# Tractive_System_Board_Rev5.net
KiCad netlist of a schematic drawn in EAGLE
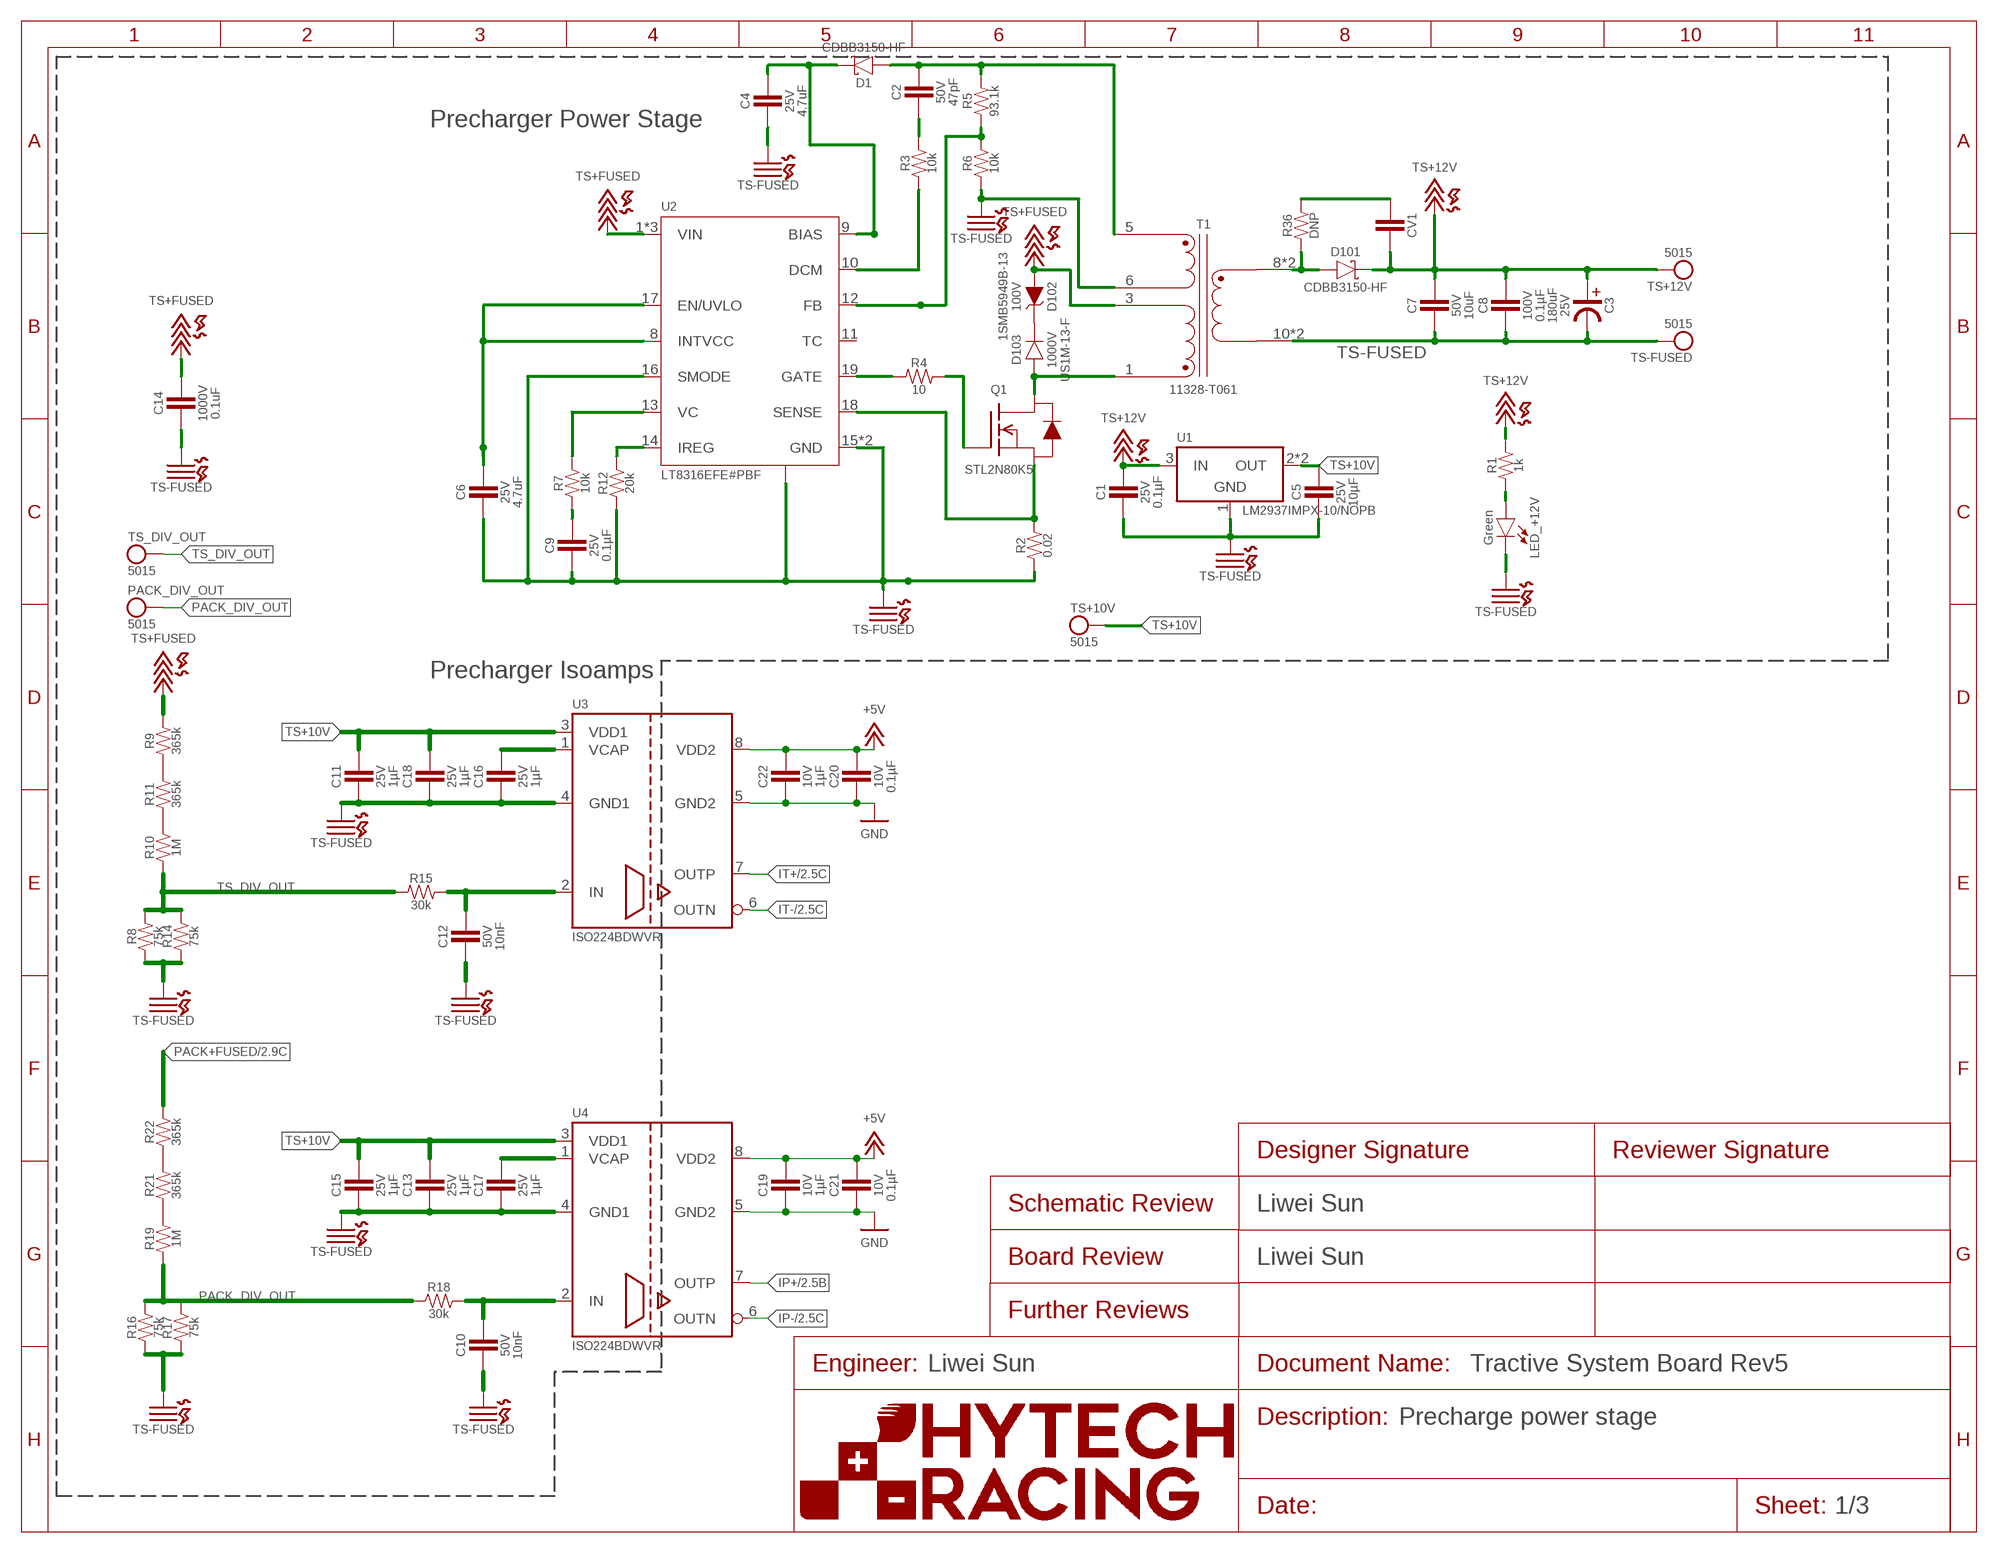
[diagram p0: schematic, sheet 1]
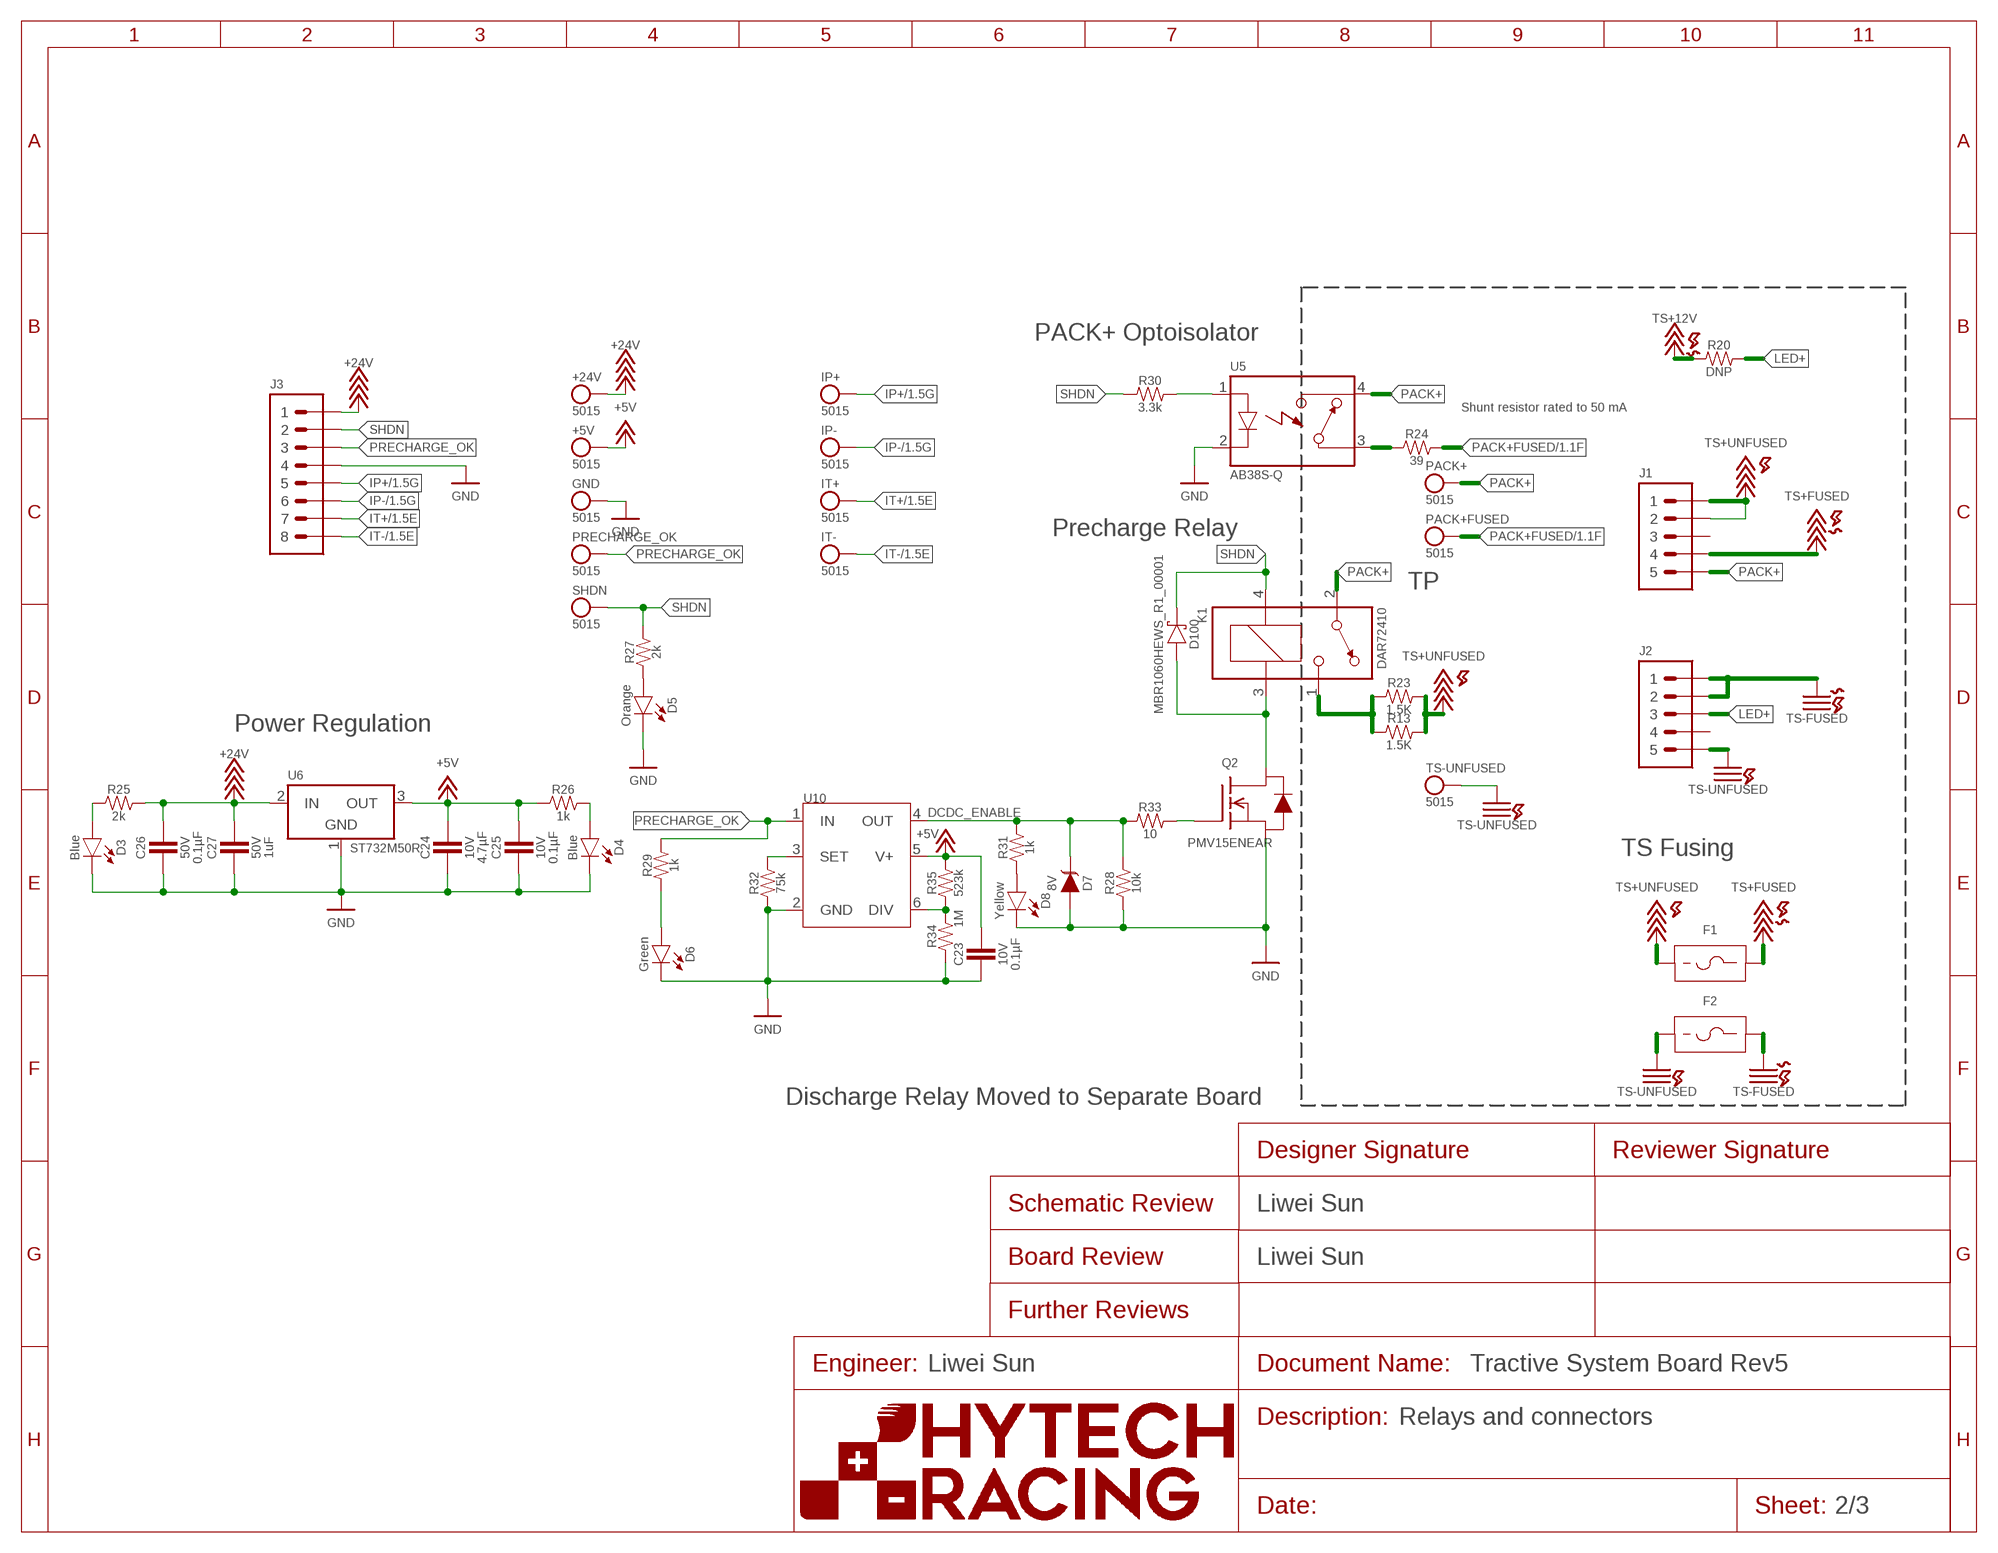
[diagram p1: schematic, sheet 2]
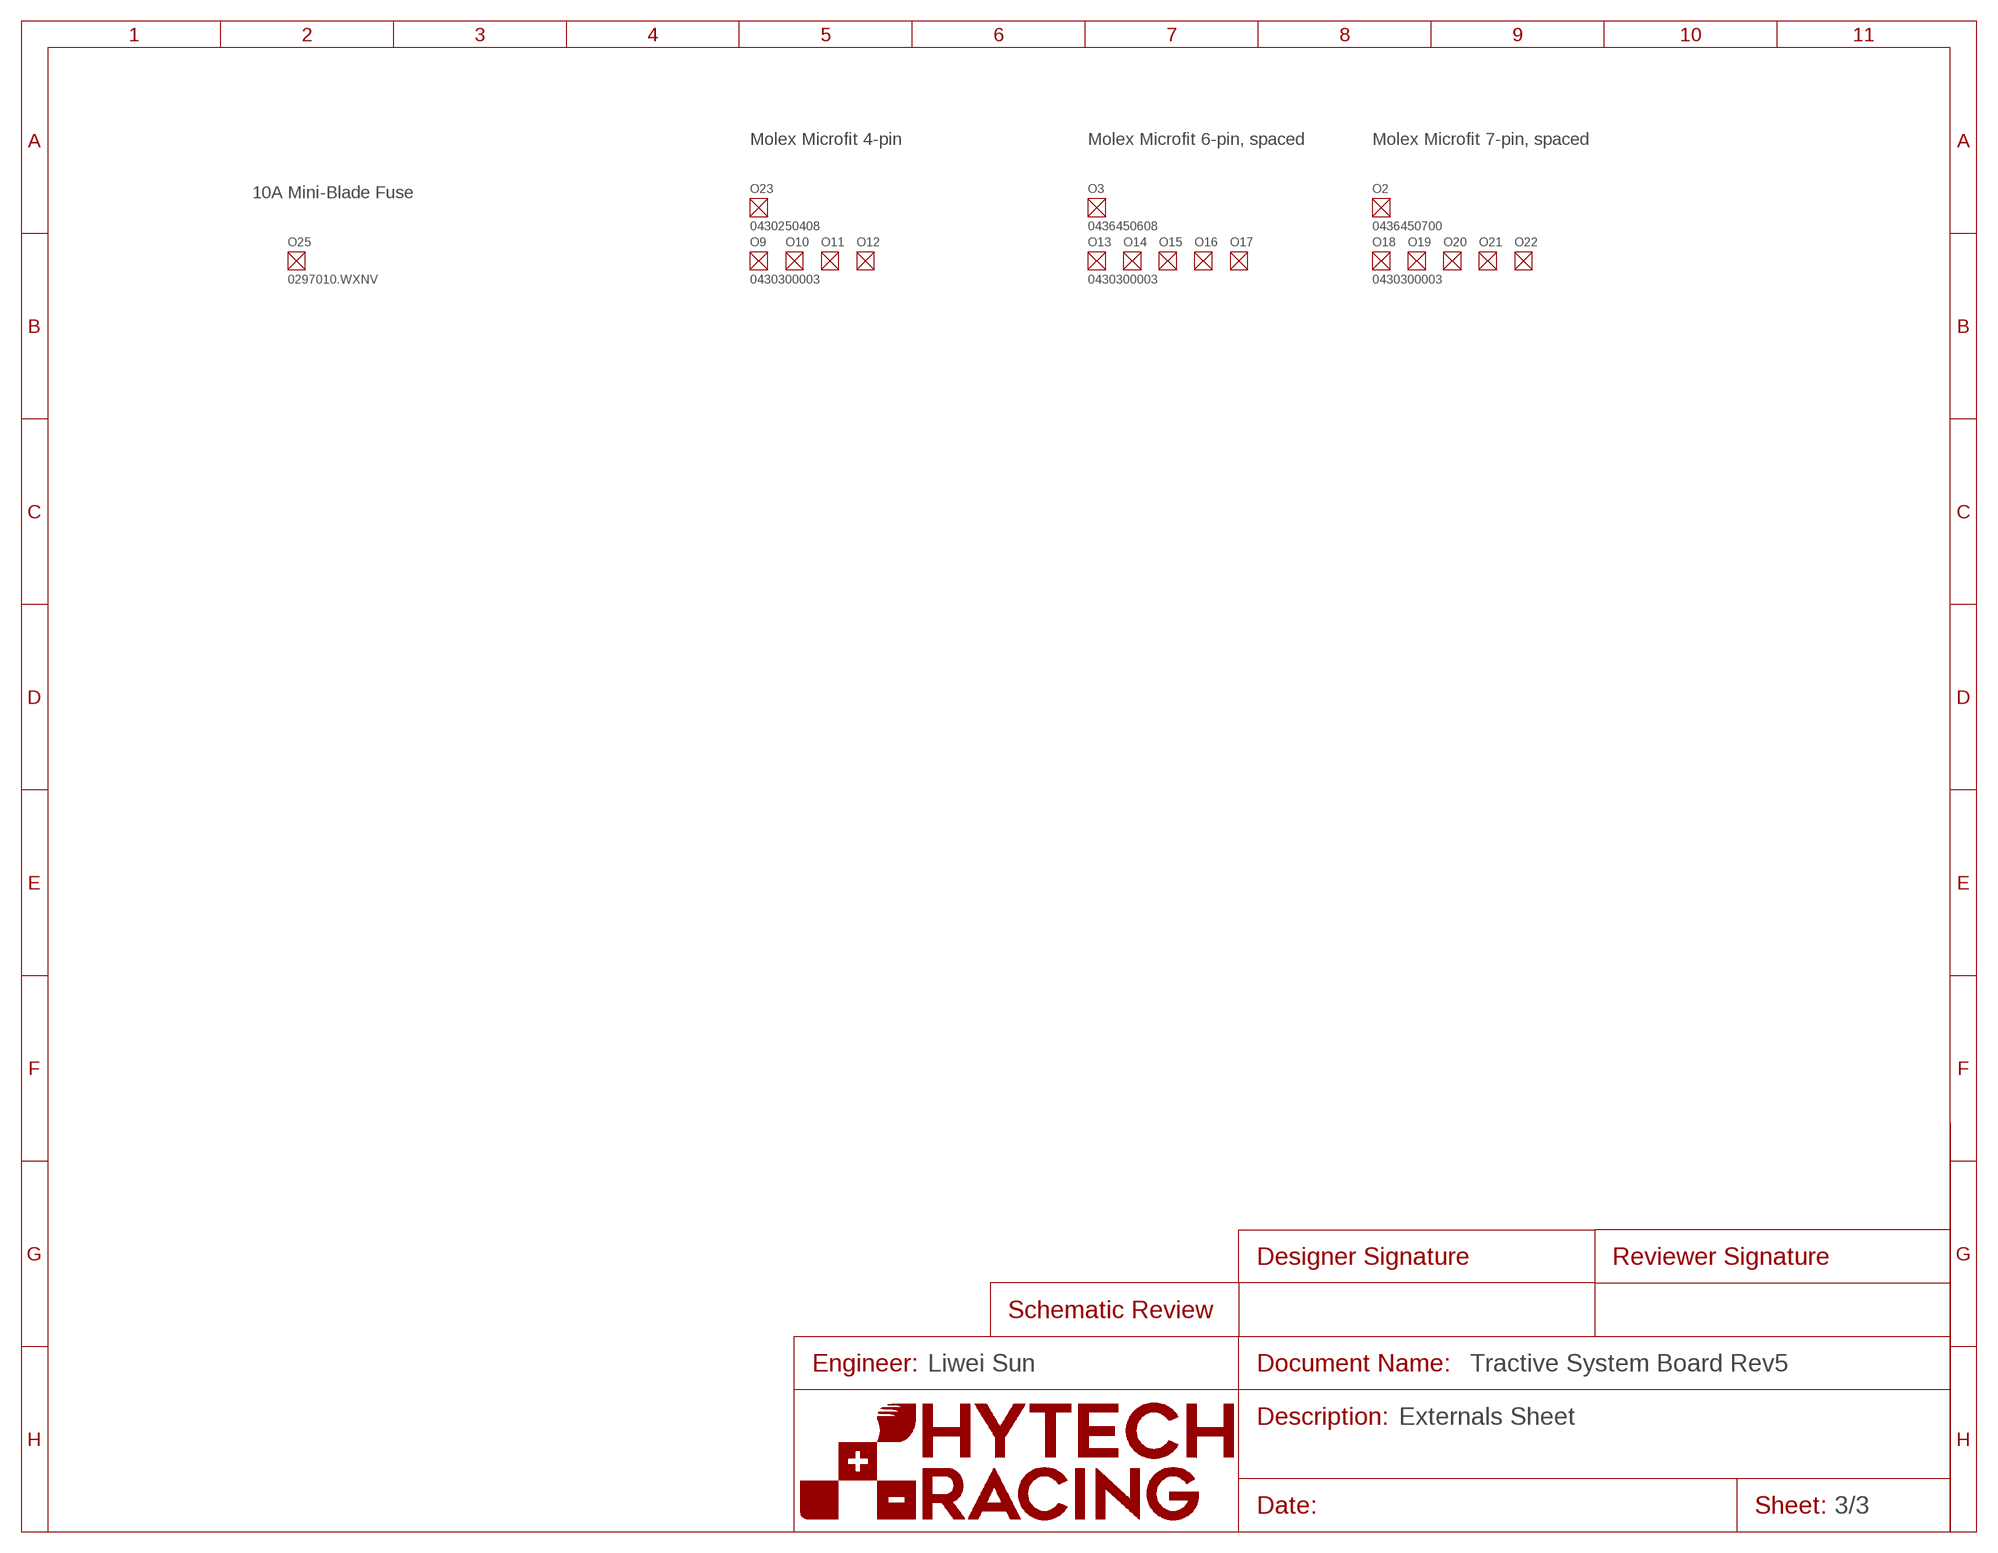
[diagram p2: schematic, sheet 3]

(export (version "E")
  (design (tool "Eeschema 10.0.6"))
  (components
    (comp (ref "C1")
      (value "CAPACITOR_0603_25V_0.1UF")
      (footprint "eagle-import:0603-CAP")
      (fields
        (field (name "CAPACITANCE") "0.1µF")
        (field (name "MANUFACTURER") "Samsung Electro-Mechanics")
        (field (name "MPN") "CL10B104KA8NNNC")
        (field (name "TOLERANCE") "10%")
        (field (name "VOLTAGE") "25V")
      )
      (libsource (lib "eagle-import") (part "CAPACITOR_?_060325V_0.1UF"))
    )
    (comp (ref "C2")
      (value "CAPACITOR_0603_50V_47PF")
      (footprint "eagle-import:0603-CAP")
      (fields
        (field (name "CAPACITANCE") "47pF")
        (field (name "MANUFACTURER") "TDK Corporation")
        (field (name "MPN") "CGA3E2NP01H470J080AA")
        (field (name "TOLERANCE") "5%")
        (field (name "VOLTAGE") "50V")
      )
      (libsource (lib "eagle-import") (part "CAPACITOR_?_060350V_47PF"))
    )
    (comp (ref "C3")
      (value "CAPACITOR_ELECTROLYTIC_A759_180UF")
      (footprint "eagle-import:A759")
      (fields
        (field (name "CAPACITANCE") "180uF")
        (field (name "MANUFACTURER") "KEMET")
        (field (name "MPN") "A759KR187M1VAAE024")
        (field (name "TOLERANCE") "20%")
        (field (name "VOLTAGE") "25V")
      )
      (libsource (lib "eagle-import") (part "CAPACITOR_ELECTROLYTIC_?_A759180UF"))
    )
    (comp (ref "C4")
      (value "CAPACITOR_0603_25V_4.7UF")
      (footprint "eagle-import:0603-CAP")
      (fields
        (field (name "CAPACITANCE") "4.7uF")
        (field (name "MANUFACTURER") "TDK Corporation")
        (field (name "MPN") " C1608X5R1E475K080AC")
        (field (name "TOLERANCE") "10%")
        (field (name "VOLTAGE") "25V")
      )
      (libsource (lib "eagle-import") (part "CAPACITOR_?_060325V_4.7UF"))
    )
    (comp (ref "C5")
      (value "CAPACITOR_0603_25V_10UF")
      (footprint "eagle-import:0603-CAP")
      (fields
        (field (name "CAPACITANCE") "10µF")
        (field (name "MANUFACTURER") "Murata Electronics")
        (field (name "MPN") "GRM188R61E106MA73D")
        (field (name "TOLERANCE") "20%")
        (field (name "VOLTAGE") "25V")
      )
      (libsource (lib "eagle-import") (part "CAPACITOR_?_060325V_10UF"))
    )
    (comp (ref "C6")
      (value "CAPACITOR_0603_25V_4.7UF")
      (footprint "eagle-import:0603-CAP")
      (fields
        (field (name "CAPACITANCE") "4.7uF")
        (field (name "MANUFACTURER") "TDK Corporation")
        (field (name "MPN") " C1608X5R1E475K080AC")
        (field (name "TOLERANCE") "10%")
        (field (name "VOLTAGE") "25V")
      )
      (libsource (lib "eagle-import") (part "CAPACITOR_?_060325V_4.7UF"))
    )
    (comp (ref "C7")
      (value "CAPACITOR_0805_50V_10UF")
      (footprint "eagle-import:0805-CAP")
      (fields
        (field (name "CAPACITANCE") "10uF")
        (field (name "MANUFACTURER") "Murata")
        (field (name "MPN") " GRM21BR61H106KE43L")
        (field (name "TOLERANCE") "10%")
        (field (name "VOLTAGE") "50V")
      )
      (libsource (lib "eagle-import") (part "CAPACITOR_?_080550V_10UF"))
    )
    (comp (ref "C8")
      (value "CAPACITOR_0603_100V_0.1UF")
      (footprint "eagle-import:0603-CAP")
      (fields
        (field (name "CAPACITANCE") "0.1µF")
        (field (name "MANUFACTURER") "Yageo")
        (field (name "MPN") "CC0603KRX7R0BB104")
        (field (name "TOLERANCE") "10%")
        (field (name "VOLTAGE") "100V")
      )
      (libsource (lib "eagle-import") (part "CAPACITOR_?_0603100V_0.1UF"))
    )
    (comp (ref "C9")
      (value "CAPACITOR_0603_25V_0.1UF")
      (footprint "eagle-import:0603-CAP")
      (fields
        (field (name "CAPACITANCE") "0.1µF")
        (field (name "MANUFACTURER") "Samsung Electro-Mechanics")
        (field (name "MPN") "CL10B104KA8NNNC")
        (field (name "TOLERANCE") "10%")
        (field (name "VOLTAGE") "25V")
      )
      (libsource (lib "eagle-import") (part "CAPACITOR_?_060325V_0.1UF"))
    )
    (comp (ref "C10")
      (value "CAPACITOR_0603_50V_10NF")
      (footprint "eagle-import:0603-CAP")
      (fields
        (field (name "CAPACITANCE") "10nF")
        (field (name "MANUFACTURER") "TDK Corporation")
        (field (name "MPN") "C1608C0G1H103J080AA")
        (field (name "TOLERANCE") "5%")
        (field (name "VOLTAGE") "50V")
      )
      (libsource (lib "eagle-import") (part "CAPACITOR_?_060350V_10NF"))
    )
    (comp (ref "C11")
      (value "CAPACITOR_0603_25V_1UF")
      (footprint "eagle-import:0603-CAP")
      (fields
        (field (name "CAPACITANCE") "1µF")
        (field (name "MANUFACTURER") "Samsung Electro-Mechanics")
        (field (name "MPN") "CL10B105KA8NNNC")
        (field (name "TOLERANCE") "10%")
        (field (name "VOLTAGE") "25V")
      )
      (libsource (lib "eagle-import") (part "CAPACITOR_?_060325V_1UF"))
    )
    (comp (ref "C12")
      (value "CAPACITOR_0603_50V_10NF")
      (footprint "eagle-import:0603-CAP")
      (fields
        (field (name "CAPACITANCE") "10nF")
        (field (name "MANUFACTURER") "TDK Corporation")
        (field (name "MPN") "C1608C0G1H103J080AA")
        (field (name "TOLERANCE") "5%")
        (field (name "VOLTAGE") "50V")
      )
      (libsource (lib "eagle-import") (part "CAPACITOR_?_060350V_10NF"))
    )
    (comp (ref "C13")
      (value "CAPACITOR_0603_25V_1UF")
      (footprint "eagle-import:0603-CAP")
      (fields
        (field (name "CAPACITANCE") "1µF")
        (field (name "MANUFACTURER") "Samsung Electro-Mechanics")
        (field (name "MPN") "CL10B105KA8NNNC")
        (field (name "TOLERANCE") "10%")
        (field (name "VOLTAGE") "25V")
      )
      (libsource (lib "eagle-import") (part "CAPACITOR_?_060325V_1UF"))
    )
    (comp (ref "C14")
      (value "CAPACITOR_1812_1000V_0.1UF")
      (footprint "eagle-import:1812-CAP")
      (fields
        (field (name "CAPACITANCE") "0.1uF")
        (field (name "MANUFACTURER") "KEMET")
        (field (name "MPN") "C1812W104KDRAC7800")
        (field (name "TOLERANCE") "10%")
        (field (name "VOLTAGE") "1000V")
      )
      (libsource (lib "eagle-import") (part "CAPACITOR_?_18121000V_0.1UF"))
    )
    (comp (ref "C15")
      (value "CAPACITOR_0603_25V_1UF")
      (footprint "eagle-import:0603-CAP")
      (fields
        (field (name "CAPACITANCE") "1µF")
        (field (name "MANUFACTURER") "Samsung Electro-Mechanics")
        (field (name "MPN") "CL10B105KA8NNNC")
        (field (name "TOLERANCE") "10%")
        (field (name "VOLTAGE") "25V")
      )
      (libsource (lib "eagle-import") (part "CAPACITOR_?_060325V_1UF"))
    )
    (comp (ref "C16")
      (value "CAPACITOR_0603_25V_1UF")
      (footprint "eagle-import:0603-CAP")
      (fields
        (field (name "CAPACITANCE") "1µF")
        (field (name "MANUFACTURER") "Samsung Electro-Mechanics")
        (field (name "MPN") "CL10B105KA8NNNC")
        (field (name "TOLERANCE") "10%")
        (field (name "VOLTAGE") "25V")
      )
      (libsource (lib "eagle-import") (part "CAPACITOR_?_060325V_1UF"))
    )
    (comp (ref "C17")
      (value "CAPACITOR_0603_25V_1UF")
      (footprint "eagle-import:0603-CAP")
      (fields
        (field (name "CAPACITANCE") "1µF")
        (field (name "MANUFACTURER") "Samsung Electro-Mechanics")
        (field (name "MPN") "CL10B105KA8NNNC")
        (field (name "TOLERANCE") "10%")
        (field (name "VOLTAGE") "25V")
      )
      (libsource (lib "eagle-import") (part "CAPACITOR_?_060325V_1UF"))
    )
    (comp (ref "C18")
      (value "CAPACITOR_0603_25V_1UF")
      (footprint "eagle-import:0603-CAP")
      (fields
        (field (name "CAPACITANCE") "1µF")
        (field (name "MANUFACTURER") "Samsung Electro-Mechanics")
        (field (name "MPN") "CL10B105KA8NNNC")
        (field (name "TOLERANCE") "10%")
        (field (name "VOLTAGE") "25V")
      )
      (libsource (lib "eagle-import") (part "CAPACITOR_?_060325V_1UF"))
    )
    (comp (ref "C19")
      (value "CAPACITOR_0603_10V_1UF")
      (footprint "eagle-import:0603-CAP")
      (fields
        (field (name "CAPACITANCE") "1µF")
        (field (name "MANUFACTURER") "Yageo")
        (field (name "MPN") "CC0603KRX7R6BB105")
        (field (name "TOLERANCE") "10%")
        (field (name "VOLTAGE") "10V")
      )
      (libsource (lib "eagle-import") (part "CAPACITOR_?_060310V_1UF"))
    )
    (comp (ref "C20")
      (value "CAPACITOR_0603_10V_0.1UF")
      (footprint "eagle-import:0603-CAP")
      (fields
        (field (name "CAPACITANCE") "0.1µF")
        (field (name "MANUFACTURER") "Vishay Vitramon")
        (field (name "MPN") "VJ0603Y104JXQPW1BC")
        (field (name "TOLERANCE") "5%")
        (field (name "VOLTAGE") "10V")
      )
      (libsource (lib "eagle-import") (part "CAPACITOR_?_060310V_0.1UF"))
    )
    (comp (ref "C21")
      (value "CAPACITOR_0603_10V_0.1UF")
      (footprint "eagle-import:0603-CAP")
      (fields
        (field (name "CAPACITANCE") "0.1µF")
        (field (name "MANUFACTURER") "Vishay Vitramon")
        (field (name "MPN") "VJ0603Y104JXQPW1BC")
        (field (name "TOLERANCE") "5%")
        (field (name "VOLTAGE") "10V")
      )
      (libsource (lib "eagle-import") (part "CAPACITOR_?_060310V_0.1UF"))
    )
    (comp (ref "C22")
      (value "CAPACITOR_0603_10V_1UF")
      (footprint "eagle-import:0603-CAP")
      (fields
        (field (name "CAPACITANCE") "1µF")
        (field (name "MANUFACTURER") "Yageo")
        (field (name "MPN") "CC0603KRX7R6BB105")
        (field (name "TOLERANCE") "10%")
        (field (name "VOLTAGE") "10V")
      )
      (libsource (lib "eagle-import") (part "CAPACITOR_?_060310V_1UF"))
    )
    (comp (ref "CV1")
      (value "CAPACITOR_VALUE")
      (footprint "eagle-import:0603-CAP")
      (libsource (lib "eagle-import") (part "CAPACITOR_VALUE"))
    )
    (comp (ref "D1")
      (value "SCHOTTKY_DO-214AA_150V")
      (footprint "eagle-import:DO-214AA")
      (fields
        (field (name "MANUFACTURER") "Comchip Technology")
        (field (name "MPN") "CDBB3150-HF")
        (field (name "VOLTAGE") "150V")
      )
      (libsource (lib "eagle-import") (part "SCHOTTKY_?_DO-214AA150V"))
    )
    (comp (ref "D101")
      (value "SCHOTTKY_DO-214AA_150V")
      (footprint "eagle-import:DO-214AA")
      (fields
        (field (name "MANUFACTURER") "Comchip Technology")
        (field (name "MPN") "CDBB3150-HF")
        (field (name "VOLTAGE") "150V")
      )
      (libsource (lib "eagle-import") (part "SCHOTTKY_?_DO-214AA150V"))
    )
    (comp (ref "D102")
      (value "ZENER_DO-214AA_100V")
      (footprint "eagle-import:DO-214AA")
      (fields
        (field (name "MANUFACTURER") "Diodes Incorporated")
        (field (name "MPN") "1SMB5949B-13")
        (field (name "VOLTAGE") "100V")
      )
      (libsource (lib "eagle-import") (part "ZENER_?_DO-214AA100V"))
    )
    (comp (ref "D103")
      (value "RECTIFIER_1000V_SMA")
      (footprint "eagle-import:SMA")
      (fields
        (field (name "MANUFACTURER") "Diodes Incorporated")
        (field (name "MPN") "US1M-13-F")
        (field (name "VOLTAGE") "1000V")
      )
      (libsource (lib "eagle-import") (part "RECTIFIER__?SMA1000V"))
    )
    (comp (ref "LED_+12V")
      (value "LED_0603_GREEN")
      (footprint "eagle-import:0603-LED")
      (fields
        (field (name "COLOR") "Green")
        (field (name "MANUFACTURER") "Kingbright")
        (field (name "MPN") "APT1608ZGCK")
      )
      (libsource (lib "eagle-import") (part "LED_?_0603GREEN"))
    )
    (comp (ref "PACK_DIV_OUT")
      (value "TEST_POINT")
      (footprint "eagle-import:5015")
      (fields (field (name "MPN") "5015") (field (name "MANUFACTURER") "Keystone Electronics"))
      (libsource (lib "eagle-import") (part "TEST_POINT"))
    )
    (comp (ref "Q1")
      (value "TRANSISTOR_N_MOS_POWERFLAT5X6_STL2N80K5")
      (footprint "eagle-import:POWERFLAT5X6")
      (fields (field (name "MANUFACTURER") "STMicroelectronics") (field (name "MPN") "STL2N80K5"))
      (libsource (lib "eagle-import") (part "TRANSISTOR_N_MOS_?_POWERFLAT5X6STL2N80K5"))
    )
    (comp (ref "R1")
      (value "RESISTOR_0603_1K")
      (footprint "eagle-import:0603-RES")
      (fields
        (field (name "MANUFACTURER") "TE Connectivity Passive Product")
        (field (name "MPN") " CPF-A-0603B1K0E")
        (field (name "POWER") "0.0625W")
        (field (name "RESISTANCE") "1k")
      )
      (libsource (lib "eagle-import") (part "RESISTOR_?_06031K"))
    )
    (comp (ref "R2")
      (value "RESISTOR_0603_0.02")
      (footprint "eagle-import:0603-RES")
      (fields
        (field (name "MANUFACTURER") "Panasonic Electronic Components")
        (field (name "MPN") "ERJ-3BWFR020V")
        (field (name "POWER") "0.33W")
        (field (name "RESISTANCE") "0.02")
      )
      (libsource (lib "eagle-import") (part "RESISTOR_?_06030.02"))
    )
    (comp (ref "R3")
      (value "RESISTOR_0603_10K")
      (footprint "eagle-import:0603-RES")
      (fields
        (field (name "MANUFACTURER") "Panasonic Electronic Components")
        (field (name "MPN") "ERA-3ARB103V")
        (field (name "POWER") "0.1W")
        (field (name "RESISTANCE") "10k")
      )
      (libsource (lib "eagle-import") (part "RESISTOR_?_060310K"))
    )
    (comp (ref "R4")
      (value "RESISTOR_0603_10")
      (footprint "eagle-import:0603-RES")
      (fields
        (field (name "MANUFACTURER") "Yageo")
        (field (name "MPN") "RC0603FR-0710RL")
        (field (name "POWER") "0.1W")
        (field (name "RESISTANCE") "10")
      )
      (libsource (lib "eagle-import") (part "RESISTOR_?_060310"))
    )
    (comp (ref "R5")
      (value "RESISTOR_0603_93.1K")
      (footprint "eagle-import:0603-RES")
      (fields
        (field (name "MANUFACTURER") "Panasonic Electronic Components")
        (field (name "MPN") "ERJ-PB3B9312V")
        (field (name "POWER") "0.2W")
        (field (name "RESISTANCE") "93.1k")
      )
      (libsource (lib "eagle-import") (part "RESISTOR_?_060393.1K"))
    )
    (comp (ref "R6")
      (value "RESISTOR_0603_10K")
      (footprint "eagle-import:0603-RES")
      (fields
        (field (name "MANUFACTURER") "Panasonic Electronic Components")
        (field (name "MPN") "ERA-3ARB103V")
        (field (name "POWER") "0.1W")
        (field (name "RESISTANCE") "10k")
      )
      (libsource (lib "eagle-import") (part "RESISTOR_?_060310K"))
    )
    (comp (ref "R7")
      (value "RESISTOR_0603_10K")
      (footprint "eagle-import:0603-RES")
      (fields
        (field (name "MANUFACTURER") "Panasonic Electronic Components")
        (field (name "MPN") "ERA-3ARB103V")
        (field (name "POWER") "0.1W")
        (field (name "RESISTANCE") "10k")
      )
      (libsource (lib "eagle-import") (part "RESISTOR_?_060310K"))
    )
    (comp (ref "R8")
      (value "RESISTOR_0805_HV75K")
      (footprint "eagle-import:0805-RES")
      (fields
        (field (name "MANUFACTURER") "Rohm Semiconductor")
        (field (name "MPN") "KTR10EZPF7502 ")
        (field (name "POWER") "0.125W")
        (field (name "RESISTANCE") "75k")
      )
      (libsource (lib "eagle-import") (part "RESISTOR_?_0805HV75K"))
    )
    (comp (ref "R9")
      (value "RESISTOR_0805_HV365K")
      (footprint "eagle-import:0805-RES")
      (fields
        (field (name "MANUFACTURER") "Rohm")
        (field (name "MPN") "KTR10EZPF3653")
        (field (name "POWER") "0.125W")
        (field (name "RESISTANCE") "365k")
      )
      (libsource (lib "eagle-import") (part "RESISTOR_?_0805HV365K"))
    )
    (comp (ref "R10")
      (value "RESISTOR_0805_HV1M")
      (footprint "eagle-import:0805-RES")
      (fields
        (field (name "MANUFACTURER") "Rohm Semiconductor")
        (field (name "MPN") "KTR10EZPF1004")
        (field (name "POWER") "0.125W")
        (field (name "RESISTANCE") "1M")
      )
      (libsource (lib "eagle-import") (part "RESISTOR_?_0805HV1M"))
    )
    (comp (ref "R11")
      (value "RESISTOR_0805_HV365K")
      (footprint "eagle-import:0805-RES")
      (fields
        (field (name "MANUFACTURER") "Rohm")
        (field (name "MPN") "KTR10EZPF3653")
        (field (name "POWER") "0.125W")
        (field (name "RESISTANCE") "365k")
      )
      (libsource (lib "eagle-import") (part "RESISTOR_?_0805HV365K"))
    )
    (comp (ref "R12")
      (value "RESISTOR_0603_20K")
      (footprint "eagle-import:0603-RES")
      (fields
        (field (name "MANUFACTURER") "Yageo")
        (field (name "MPN") "RC0603FR-0720KL")
        (field (name "POWER") "0.1 W")
        (field (name "RESISTANCE") "20k")
      )
      (libsource (lib "eagle-import") (part "RESISTOR_?_060320K"))
    )
    (comp (ref "R14")
      (value "RESISTOR_0805_HV75K")
      (footprint "eagle-import:0805-RES")
      (fields
        (field (name "MANUFACTURER") "Rohm Semiconductor")
        (field (name "MPN") "KTR10EZPF7502 ")
        (field (name "POWER") "0.125W")
        (field (name "RESISTANCE") "75k")
      )
      (libsource (lib "eagle-import") (part "RESISTOR_?_0805HV75K"))
    )
    (comp (ref "R15")
      (value "RESISTOR_0603_")
      (footprint "eagle-import:0603-RES")
      (fields
        (field (name "MANUFACTURER") "Panasonic Electronic Components")
        (field (name "MPN") "ERA-3ARB303V")
        (field (name "POWER") "0.1W")
        (field (name "RESISTANCE") "30k")
      )
      (libsource (lib "eagle-import") (part "RESISTOR_?_060330K"))
    )
    (comp (ref "R16")
      (value "RESISTOR_0805_HV75K")
      (footprint "eagle-import:0805-RES")
      (fields
        (field (name "MANUFACTURER") "Rohm Semiconductor")
        (field (name "MPN") "KTR10EZPF7502 ")
        (field (name "POWER") "0.125W")
        (field (name "RESISTANCE") "75k")
      )
      (libsource (lib "eagle-import") (part "RESISTOR_?_0805HV75K"))
    )
    (comp (ref "R17")
      (value "RESISTOR_0805_HV75K")
      (footprint "eagle-import:0805-RES")
      (fields
        (field (name "MANUFACTURER") "Rohm Semiconductor")
        (field (name "MPN") "KTR10EZPF7502 ")
        (field (name "POWER") "0.125W")
        (field (name "RESISTANCE") "75k")
      )
      (libsource (lib "eagle-import") (part "RESISTOR_?_0805HV75K"))
    )
    (comp (ref "R18")
      (value "RESISTOR_0603_")
      (footprint "eagle-import:0603-RES")
      (fields
        (field (name "MANUFACTURER") "Panasonic Electronic Components")
        (field (name "MPN") "ERA-3ARB303V")
        (field (name "POWER") "0.1W")
        (field (name "RESISTANCE") "30k")
      )
      (libsource (lib "eagle-import") (part "RESISTOR_?_060330K"))
    )
    (comp (ref "R19")
      (value "RESISTOR_0805_HV1M")
      (footprint "eagle-import:0805-RES")
      (fields
        (field (name "MANUFACTURER") "Rohm Semiconductor")
        (field (name "MPN") "KTR10EZPF1004")
        (field (name "POWER") "0.125W")
        (field (name "RESISTANCE") "1M")
      )
      (libsource (lib "eagle-import") (part "RESISTOR_?_0805HV1M"))
    )
    (comp (ref "R21")
      (value "RESISTOR_0805_HV365K")
      (footprint "eagle-import:0805-RES")
      (fields
        (field (name "MANUFACTURER") "Rohm")
        (field (name "MPN") "KTR10EZPF3653")
        (field (name "POWER") "0.125W")
        (field (name "RESISTANCE") "365k")
      )
      (libsource (lib "eagle-import") (part "RESISTOR_?_0805HV365K"))
    )
    (comp (ref "R22")
      (value "RESISTOR_0805_HV365K")
      (footprint "eagle-import:0805-RES")
      (fields
        (field (name "MANUFACTURER") "Rohm")
        (field (name "MPN") "KTR10EZPF3653")
        (field (name "POWER") "0.125W")
        (field (name "RESISTANCE") "365k")
      )
      (libsource (lib "eagle-import") (part "RESISTOR_?_0805HV365K"))
    )
    (comp (ref "R36")
      (value "RESISTOR_0603_DNP")
      (footprint "eagle-import:0603-RES")
      (fields (field (name "RESISTANCE") "DNP"))
      (libsource (lib "eagle-import") (part "RESISTOR_?_0603DNP"))
    )
    (comp (ref "T1")
      (value "TRANSFORMER(3W)")
      (footprint "eagle-import:PQ2620")
      (fields (field (name "MPN") "11328-T061") (field (name "MANUFACTURER") "Sumida"))
      (libsource (lib "eagle-import") (part "TRANSFORMER(3W)"))
    )
    (comp (ref "TS+10V")
      (value "TEST_POINT")
      (footprint "eagle-import:5015")
      (fields (field (name "MPN") "5015") (field (name "MANUFACTURER") "Keystone Electronics"))
      (libsource (lib "eagle-import") (part "TEST_POINT"))
    )
    (comp (ref "TS+12V")
      (value "TEST_POINT")
      (footprint "eagle-import:5015")
      (fields (field (name "MPN") "5015") (field (name "MANUFACTURER") "Keystone Electronics"))
      (libsource (lib "eagle-import") (part "TEST_POINT"))
    )
    (comp (ref "TS-FUSED")
      (value "TEST_POINT")
      (footprint "eagle-import:5015")
      (fields (field (name "MPN") "5015") (field (name "MANUFACTURER") "Keystone Electronics"))
      (libsource (lib "eagle-import") (part "TEST_POINT"))
    )
    (comp (ref "TS_DIV_OUT")
      (value "TEST_POINT")
      (footprint "eagle-import:5015")
      (fields (field (name "MPN") "5015") (field (name "MANUFACTURER") "Keystone Electronics"))
      (libsource (lib "eagle-import") (part "TEST_POINT"))
    )
    (comp (ref "U1")
      (value "VOLTAGE_REGULATOR_SOT-223_10V")
      (footprint "eagle-import:SOT-223")
      (fields (field (name "MANUFACTURER") "Texas Instruments") (field (name "MPN") " LM2937IMPX-10/NOPB"))
      (libsource (lib "eagle-import") (part "VOLTAGE_REGULATOR_?_SOT-22310V"))
    )
    (comp (ref "U2")
      (value "LT8316")
      (footprint "eagle-import:TSSOP-20(16)")
      (fields (field (name "MPN") "LT8316EFE#PBF") (field (name "MANUFACTURER") "Analog Devices"))
      (libsource (lib "eagle-import") (part "LT8316"))
    )
    (comp (ref "U3")
      (value "ISO224B_AIRGAP")
      (footprint "eagle-import:SOIC-08(WIDE,0.295_)-AIRGAP")
      (fields (field (name "MANUFACTURER") "Texas Instruments") (field (name "MPN") "ISO224BDWVR"))
      (libsource (lib "eagle-import") (part "ISO224_AIRGAPB"))
    )
    (comp (ref "U4")
      (value "ISO224B_AIRGAP")
      (footprint "eagle-import:SOIC-08(WIDE,0.295_)-AIRGAP")
      (fields (field (name "MANUFACTURER") "Texas Instruments") (field (name "MPN") "ISO224BDWVR"))
      (libsource (lib "eagle-import") (part "ISO224_AIRGAPB"))
    )
    (comp (ref "+5V")
      (value "TEST_POINT")
      (footprint "eagle-import:5015")
      (fields (field (name "MPN") "5015") (field (name "MANUFACTURER") "Keystone Electronics"))
      (libsource (lib "eagle-import") (part "TEST_POINT"))
    )
    (comp (ref "+24V")
      (value "TEST_POINT")
      (footprint "eagle-import:5015")
      (fields (field (name "MPN") "5015") (field (name "MANUFACTURER") "Keystone Electronics"))
      (libsource (lib "eagle-import") (part "TEST_POINT"))
    )
    (comp (ref "C23")
      (value "CAPACITOR_0603_10V_0.1UF")
      (footprint "eagle-import:0603-CAP")
      (fields
        (field (name "CAPACITANCE") "0.1µF")
        (field (name "MANUFACTURER") "Vishay Vitramon")
        (field (name "MPN") "VJ0603Y104JXQPW1BC")
        (field (name "TOLERANCE") "5%")
        (field (name "VOLTAGE") "10V")
      )
      (libsource (lib "eagle-import") (part "CAPACITOR_?_060310V_0.1UF"))
    )
    (comp (ref "C24")
      (value "CAPACITOR_0603_10V_4.7UF")
      (footprint "eagle-import:0603-CAP")
      (fields
        (field (name "CAPACITANCE") "4.7µF")
        (field (name "MANUFACTURER") "Samsung Electro-Mechanics")
        (field (name "MPN") "CL10A475KP8NNNC")
        (field (name "TOLERANCE") "10%")
        (field (name "VOLTAGE") "10V")
      )
      (libsource (lib "eagle-import") (part "CAPACITOR_?_060310V_4.7UF"))
    )
    (comp (ref "C25")
      (value "CAPACITOR_0603_10V_0.1UF")
      (footprint "eagle-import:0603-CAP")
      (fields
        (field (name "CAPACITANCE") "0.1µF")
        (field (name "MANUFACTURER") "Vishay Vitramon")
        (field (name "MPN") "VJ0603Y104JXQPW1BC")
        (field (name "TOLERANCE") "5%")
        (field (name "VOLTAGE") "10V")
      )
      (libsource (lib "eagle-import") (part "CAPACITOR_?_060310V_0.1UF"))
    )
    (comp (ref "C26")
      (value "CAPACITOR_0603_50V_0.1UF")
      (footprint "eagle-import:0603-CAP")
      (fields
        (field (name "CAPACITANCE") "0.1µF")
        (field (name "MANUFACTURER") "Yageo")
        (field (name "MPN") "CC0603KRX7R9BB104")
        (field (name "TOLERANCE") "10%")
        (field (name "VOLTAGE") "50V")
      )
      (libsource (lib "eagle-import") (part "CAPACITOR_?_060350V_0.1UF"))
    )
    (comp (ref "C27")
      (value "CAPACITOR_0603_50V_1UF")
      (footprint "eagle-import:0603-CAP")
      (fields
        (field (name "CAPACITANCE") "1uF")
        (field (name "MANUFACTURER") "Taiyo Yuden")
        (field (name "MPN") "UMK107BJ105KA-T")
        (field (name "TOLERANCE") "10%")
        (field (name "VOLTAGE") "50V")
      )
      (libsource (lib "eagle-import") (part "CAPACITOR_?_060350V_1UF"))
    )
    (comp (ref "D3")
      (value "LED_0603_BLUE")
      (footprint "eagle-import:0603-LED")
      (fields
        (field (name "COLOR") "Blue")
        (field (name "MANUFACTURER") "Kingbright")
        (field (name "MPN") "APT1608VBC/D")
      )
      (libsource (lib "eagle-import") (part "LED_?_0603BLUE"))
    )
    (comp (ref "D4")
      (value "LED_0603_BLUE")
      (footprint "eagle-import:0603-LED")
      (fields
        (field (name "COLOR") "Blue")
        (field (name "MANUFACTURER") "Kingbright")
        (field (name "MPN") "APT1608VBC/D")
      )
      (libsource (lib "eagle-import") (part "LED_?_0603BLUE"))
    )
    (comp (ref "D5")
      (value "LED_0603_ORANGE")
      (footprint "eagle-import:0603-LED")
      (fields
        (field (name "COLOR") "Orange")
        (field (name "MANUFACTURER") "Kingbright")
        (field (name "MPN") "APT1608SECK")
      )
      (libsource (lib "eagle-import") (part "LED_?_0603ORANGE"))
    )
    (comp (ref "D6")
      (value "LED_0603_GREEN")
      (footprint "eagle-import:0603-LED")
      (fields
        (field (name "COLOR") "Green")
        (field (name "MANUFACTURER") "Kingbright")
        (field (name "MPN") "APT1608ZGCK")
      )
      (libsource (lib "eagle-import") (part "LED_?_0603GREEN"))
    )
    (comp (ref "D7")
      (value "TVS__8V")
      (footprint "eagle-import:SOT-23")
      (fields
        (field (name "MANUFACTURER") "Vishay General Semiconductor - Diodes Division")
        (field (name "MPN") "GSOT08-E3-08")
        (field (name "VOLTAGE") "8V")
      )
      (libsource (lib "eagle-import") (part "TVS_?_8V"))
    )
    (comp (ref "D8")
      (value "LED_0603_YELLOW")
      (footprint "eagle-import:0603-LED")
      (fields
        (field (name "COLOR") "Yellow")
        (field (name "MANUFACTURER") "Kingbright")
        (field (name "MPN") "APT1608SYCK/J3-PRV")
      )
      (libsource (lib "eagle-import") (part "LED_?_0603YELLOW"))
    )
    (comp (ref "D100")
      (value "SCHOTTKY_SOD323_60V")
      (footprint "eagle-import:SOD-323")
      (fields
        (field (name "MANUFACTURER") "Panjit International Inc.")
        (field (name "MPN") "MBR1060HEWS_R1_00001")
        (field (name "VOLTAGE") "60V")
      )
      (libsource (lib "eagle-import") (part "SCHOTTKY_?_SOD32360V"))
    )
    (comp (ref "F1")
      (value "FUSE_HOLDER_122")
      (footprint "eagle-import:122")
      (fields (field (name "MPN") "01220088Z") (field (name "MANUFACTURER") "Littelfuse"))
      (libsource (lib "eagle-import") (part "FUSE_HOLDER_122"))
    )
    (comp (ref "F2")
      (value "FUSE_HOLDER_122")
      (footprint "eagle-import:122")
      (fields (field (name "MPN") "01220088Z") (field (name "MANUFACTURER") "Littelfuse"))
      (libsource (lib "eagle-import") (part "FUSE_HOLDER_122"))
    )
    (comp (ref "GND")
      (value "TEST_POINT")
      (footprint "eagle-import:5015")
      (fields (field (name "MPN") "5015") (field (name "MANUFACTURER") "Keystone Electronics"))
      (libsource (lib "eagle-import") (part "TEST_POINT"))
    )
    (comp (ref "IP+")
      (value "TEST_POINT")
      (footprint "eagle-import:5015")
      (fields (field (name "MPN") "5015") (field (name "MANUFACTURER") "Keystone Electronics"))
      (libsource (lib "eagle-import") (part "TEST_POINT"))
    )
    (comp (ref "IP-")
      (value "TEST_POINT")
      (footprint "eagle-import:5015")
      (fields (field (name "MPN") "5015") (field (name "MANUFACTURER") "Keystone Electronics"))
      (libsource (lib "eagle-import") (part "TEST_POINT"))
    )
    (comp (ref "IT+")
      (value "TEST_POINT")
      (footprint "eagle-import:5015")
      (fields (field (name "MPN") "5015") (field (name "MANUFACTURER") "Keystone Electronics"))
      (libsource (lib "eagle-import") (part "TEST_POINT"))
    )
    (comp (ref "IT-")
      (value "TEST_POINT")
      (footprint "eagle-import:5015")
      (fields (field (name "MPN") "5015") (field (name "MANUFACTURER") "Keystone Electronics"))
      (libsource (lib "eagle-import") (part "TEST_POINT"))
    )
    (comp (ref "J1")
      (value "CONNECTOR-5_MICRO_V7S_")
      (footprint "eagle-import:MOLEX_MICROFIT_PTH_VERTICAL_07_SINGLE_SPACED")
      (fields (field (name "MPN") "2165713007") (field (name "MANUFACTURER") "Molex"))
      (libsource (lib "eagle-import") (part "CONNECTOR-5_?_MICRO_V7S"))
    )
    (comp (ref "J2")
      (value "CONNECTOR-5_MICRO_V6S_")
      (footprint "eagle-import:MOLEX_MICROFIT_PTH_VERTICAL_06_SINGLE_SPACED")
      (fields (field (name "MPN") "2165713006") (field (name "MANUFACTURER") "Molex"))
      (libsource (lib "eagle-import") (part "CONNECTOR-5_?_MICRO_V6S"))
    )
    (comp (ref "J3")
      (value "CONNECTOR-8_μF_T_V_BLACK")
      (footprint "eagle-import:MOLEX_MICROFIT_PTH_VERTICAL_08_DUAL")
      (fields (field (name "MANUFACTURER") "Molex") (field (name "MPN") "430450814"))
      (libsource (lib "eagle-import") (part "CONNECTOR-8_?_μF_T_VBLACK"))
    )
    (comp (ref "K1")
      (value "RELAY_SPST_NO_D_24")
      (footprint "eagle-import:D")
      (fields (field (name "MANUFACTURER") "Sensata-Cynergy3") (field (name "MPN") "DAR72410"))
      (libsource (lib "eagle-import") (part "RELAY_SPST_NO_?D_24"))
    )
    (comp (ref "PACK+")
      (value "TEST_POINT")
      (footprint "eagle-import:5015")
      (fields (field (name "MPN") "5015") (field (name "MANUFACTURER") "Keystone Electronics"))
      (libsource (lib "eagle-import") (part "TEST_POINT"))
    )
    (comp (ref "PACK+FUSED")
      (value "TEST_POINT")
      (footprint "eagle-import:5015")
      (fields (field (name "MPN") "5015") (field (name "MANUFACTURER") "Keystone Electronics"))
      (libsource (lib "eagle-import") (part "TEST_POINT"))
    )
    (comp (ref "PRECHARGE_OK")
      (value "TEST_POINT")
      (footprint "eagle-import:5015")
      (fields (field (name "MPN") "5015") (field (name "MANUFACTURER") "Keystone Electronics"))
      (libsource (lib "eagle-import") (part "TEST_POINT"))
    )
    (comp (ref "Q2")
      (value "TRANSISTOR_N_MOS__PMV15ENEA")
      (footprint "eagle-import:SOT-23")
      (fields (field (name "MANUFACTURER") "Nexperia USA Inc.") (field (name "MPN") "PMV15ENEAR"))
      (libsource (lib "eagle-import") (part "TRANSISTOR_N_MOS_?_PMV15ENEA"))
    )
    (comp (ref "R13")
      (value "RESISTOR_B20-SHORTENED_1.5K")
      (footprint "eagle-import:B20-SHORTENED")
      (fields
        (field (name "MANUFACTURER") "Ohmite")
        (field (name "MPN") "B20J1K5E")
        (field (name "POWER") "20W")
        (field (name "RESISTANCE") "1.5K")
      )
      (libsource (lib "eagle-import") (part "RESISTOR_?_B20-SHORTENED1.5K"))
    )
    (comp (ref "R20")
      (value "RESISTOR_0603_DNP")
      (footprint "eagle-import:0603-RES")
      (fields (field (name "RESISTANCE") "DNP"))
      (libsource (lib "eagle-import") (part "RESISTOR_?_0603DNP"))
    )
    (comp (ref "R23")
      (value "RESISTOR_B20-SHORTENED_1.5K")
      (footprint "eagle-import:B20-SHORTENED")
      (fields
        (field (name "MANUFACTURER") "Ohmite")
        (field (name "MPN") "B20J1K5E")
        (field (name "POWER") "20W")
        (field (name "RESISTANCE") "1.5K")
      )
      (libsource (lib "eagle-import") (part "RESISTOR_?_B20-SHORTENED1.5K"))
    )
    (comp (ref "R24")
      (value "RESISTOR_0603_39")
      (footprint "eagle-import:0603-RES")
      (fields
        (field (name "MANUFACTURER") "Yageo")
        (field (name "MPN") "RT0603BRD0739RL")
        (field (name "POWER") "0.1W")
        (field (name "RESISTANCE") "39")
      )
      (libsource (lib "eagle-import") (part "RESISTOR_?_060339"))
    )
    (comp (ref "R25")
      (value "RESISTOR_0603_2K")
      (footprint "eagle-import:0603-RES")
      (fields
        (field (name "MANUFACTURER") "Panasonic Electronic Components")
        (field (name "MPN") "ERJ-UP3F2001V")
        (field (name "POWER") "0.25W")
        (field (name "RESISTANCE") "2k")
      )
      (libsource (lib "eagle-import") (part "RESISTOR_?_06032K"))
    )
    (comp (ref "R26")
      (value "RESISTOR_0603_1K")
      (footprint "eagle-import:0603-RES")
      (fields
        (field (name "MANUFACTURER") "TE Connectivity Passive Product")
        (field (name "MPN") " CPF-A-0603B1K0E")
        (field (name "POWER") "0.0625W")
        (field (name "RESISTANCE") "1k")
      )
      (libsource (lib "eagle-import") (part "RESISTOR_?_06031K"))
    )
    (comp (ref "R27")
      (value "RESISTOR_0603_2K")
      (footprint "eagle-import:0603-RES")
      (fields
        (field (name "MANUFACTURER") "Panasonic Electronic Components")
        (field (name "MPN") "ERJ-UP3F2001V")
        (field (name "POWER") "0.25W")
        (field (name "RESISTANCE") "2k")
      )
      (libsource (lib "eagle-import") (part "RESISTOR_?_06032K"))
    )
    (comp (ref "R28")
      (value "RESISTOR_0603_10K")
      (footprint "eagle-import:0603-RES")
      (fields
        (field (name "MANUFACTURER") "Panasonic Electronic Components")
        (field (name "MPN") "ERA-3ARB103V")
        (field (name "POWER") "0.1W")
        (field (name "RESISTANCE") "10k")
      )
      (libsource (lib "eagle-import") (part "RESISTOR_?_060310K"))
    )
    (comp (ref "R29")
      (value "RESISTOR_0603_1K")
      (footprint "eagle-import:0603-RES")
      (fields
        (field (name "MANUFACTURER") "TE Connectivity Passive Product")
        (field (name "MPN") " CPF-A-0603B1K0E")
        (field (name "POWER") "0.0625W")
        (field (name "RESISTANCE") "1k")
      )
      (libsource (lib "eagle-import") (part "RESISTOR_?_06031K"))
    )
    (comp (ref "R30")
      (value "RESISTOR_0603_3.3K")
      (footprint "eagle-import:0603-RES")
      (fields
        (field (name "MANUFACTURER") "Panasonic Electronic Components")
        (field (name "MPN") "ERJ-PB3D3301V")
        (field (name "POWER") "0.2W")
        (field (name "RESISTANCE") "3.3k")
      )
      (libsource (lib "eagle-import") (part "RESISTOR_?_06033.3K"))
    )
    (comp (ref "R31")
      (value "RESISTOR_0603_1K")
      (footprint "eagle-import:0603-RES")
      (fields
        (field (name "MANUFACTURER") "TE Connectivity Passive Product")
        (field (name "MPN") " CPF-A-0603B1K0E")
        (field (name "POWER") "0.0625W")
        (field (name "RESISTANCE") "1k")
      )
      (libsource (lib "eagle-import") (part "RESISTOR_?_06031K"))
    )
    (comp (ref "R32")
      (value "RESISTOR_0603_75K")
      (footprint "eagle-import:0603-RES")
      (fields
        (field (name "MANUFACTURER") "Yageo")
        (field (name "MPN") "RT0603BRE0775KL")
        (field (name "POWER") "0.1W")
        (field (name "RESISTANCE") "75k")
      )
      (libsource (lib "eagle-import") (part "RESISTOR_?_060375K"))
    )
    (comp (ref "R33")
      (value "RESISTOR_0603_10")
      (footprint "eagle-import:0603-RES")
      (fields
        (field (name "MANUFACTURER") "Yageo")
        (field (name "MPN") "RC0603FR-0710RL")
        (field (name "POWER") "0.1W")
        (field (name "RESISTANCE") "10")
      )
      (libsource (lib "eagle-import") (part "RESISTOR_?_060310"))
    )
    (comp (ref "R34")
      (value "RESISTOR_0805_1M")
      (footprint "eagle-import:0805-RES")
      (fields
        (field (name "MANUFACTURER") "Panasonic Electronic Components")
        (field (name "MPN") "ERJ-PB6B1004V")
        (field (name "POWER") "0.25W")
        (field (name "RESISTANCE") "1M")
      )
      (libsource (lib "eagle-import") (part "RESISTOR_?_08051M"))
    )
    (comp (ref "R35")
      (value "RESISTOR_0805_523K")
      (footprint "eagle-import:0805-RES")
      (fields
        (field (name "MANUFACTURER") "Panasonic Electronic Components")
        (field (name "MPN") "ERJ-PB6B5233V")
        (field (name "POWER") "0.25W")
        (field (name "RESISTANCE") "523k")
      )
      (libsource (lib "eagle-import") (part "RESISTOR_?_0805523K"))
    )
    (comp (ref "SHDN")
      (value "TEST_POINT")
      (footprint "eagle-import:5015")
      (fields (field (name "MPN") "5015") (field (name "MANUFACTURER") "Keystone Electronics"))
      (libsource (lib "eagle-import") (part "TEST_POINT"))
    )
    (comp (ref "TS-UNFUSED")
      (value "TEST_POINT")
      (footprint "eagle-import:5015")
      (fields (field (name "MPN") "5015") (field (name "MANUFACTURER") "Keystone Electronics"))
      (libsource (lib "eagle-import") (part "TEST_POINT"))
    )
    (comp (ref "U5")
      (value "RELAY_SOLIDSTATE_NO_AB38S-Q-AIRGAP")
      (footprint "eagle-import:SOP-04-AIRGAP")
      (fields
        (field (name "MPN") "AB38S-Q")
        (field (name "MANUFACTURER") "Comus International")
        (field (name "VOLTAGE") "600V")
      )
      (libsource (lib "eagle-import") (part "RELAY_SOLIDSTATE_NO_AB38S-Q-AIRGAP"))
    )
    (comp (ref "U6")
      (value "VOLTAGE_REGULATOR_SOT-23-5_5V")
      (footprint "eagle-import:SOT-23-5")
      (fields (field (name "MANUFACTURER") "STMicroelectronics") (field (name "MPN") "ST732M50R"))
      (libsource (lib "eagle-import") (part "VOLTAGE_REGULATOR_?_SOT-23-55V"))
    )
    (comp (ref "U10")
      (value "LTC6994-2")
      (footprint "eagle-import:SOT-23-6")
      (libsource (lib "eagle-import") (part "LTC6994-2"))
    )
  )
  (nets
    (net (code "1") (name "+5V") (class "Default")
      (node (ref "+5V") (pin "1") (pinfunction "1_1") (pintype "passive"))
      (node (ref "C19") (pin "1") (pinfunction "1_1") (pintype "passive"))
      (node (ref "C20") (pin "1") (pinfunction "1_1") (pintype "passive"))
      (node (ref "C21") (pin "1") (pinfunction "1_1") (pintype "passive"))
      (node (ref "C22") (pin "1") (pinfunction "1_1") (pintype "passive"))
      (node (ref "C23") (pin "1") (pinfunction "1_1") (pintype "passive"))
      (node (ref "C24") (pin "1") (pinfunction "1_1") (pintype "passive"))
      (node (ref "C25") (pin "1") (pinfunction "1_1") (pintype "passive"))
      (node (ref "R26") (pin "1") (pinfunction "1_1") (pintype "passive"))
      (node (ref "R35") (pin "2") (pinfunction "2_2") (pintype "passive"))
      (node (ref "U10") (pin "5") (pinfunction "V+_5") (pintype "power_in"))
      (node (ref "U3") (pin "8") (pinfunction "VDD2_8") (pintype "power_in"))
      (node (ref "U4") (pin "8") (pinfunction "VDD2_8") (pintype "power_in"))
      (node (ref "U6") (pin "3") (pinfunction "OUT_3") (pintype "power_in"))
    )
    (net (code "2") (name "+24V") (class "Default")
      (node (ref "+24V") (pin "1") (pinfunction "1_1") (pintype "passive"))
      (node (ref "C26") (pin "1") (pinfunction "1_1") (pintype "passive"))
      (node (ref "C27") (pin "1") (pinfunction "1_1") (pintype "passive"))
      (node (ref "J3") (pin "1") (pinfunction "1_1") (pintype "passive"))
      (node (ref "R25") (pin "2") (pinfunction "2_2") (pintype "passive"))
      (node (ref "U6") (pin "2") (pinfunction "IN_2") (pintype "power_in"))
    )
    (net (code "3") (name "DCDC_ENABLE") (class "Default")
      (node (ref "D7") (pin "3") (pinfunction "C_3") (pintype "passive"))
      (node (ref "R28") (pin "2") (pinfunction "2_2") (pintype "passive"))
      (node (ref "R31") (pin "2") (pinfunction "2_2") (pintype "passive"))
      (node (ref "R33") (pin "1") (pinfunction "1_1") (pintype "passive"))
      (node (ref "U10") (pin "4") (pinfunction "OUT_4") (pintype "bidirectional"))
    )
    (net (code "4") (name "GND") (class "Default")
      (node (ref "C19") (pin "2") (pinfunction "2_2") (pintype "passive"))
      (node (ref "C20") (pin "2") (pinfunction "2_2") (pintype "passive"))
      (node (ref "C21") (pin "2") (pinfunction "2_2") (pintype "passive"))
      (node (ref "C22") (pin "2") (pinfunction "2_2") (pintype "passive"))
      (node (ref "C23") (pin "2") (pinfunction "2_2") (pintype "passive"))
      (node (ref "C24") (pin "2") (pinfunction "2_2") (pintype "passive"))
      (node (ref "C25") (pin "2") (pinfunction "2_2") (pintype "passive"))
      (node (ref "C26") (pin "2") (pinfunction "2_2") (pintype "passive"))
      (node (ref "C27") (pin "2") (pinfunction "2_2") (pintype "passive"))
      (node (ref "D3") (pin "1") (pinfunction "C_1") (pintype "passive"))
      (node (ref "D4") (pin "1") (pinfunction "C_1") (pintype "passive"))
      (node (ref "D5") (pin "1") (pinfunction "C_1") (pintype "passive"))
      (node (ref "D6") (pin "1") (pinfunction "C_1") (pintype "passive"))
      (node (ref "D7") (pin "1") (pinfunction "A_1") (pintype "passive"))
      (node (ref "D8") (pin "1") (pinfunction "C_1") (pintype "passive"))
      (node (ref "GND") (pin "1") (pinfunction "1_1") (pintype "passive"))
      (node (ref "J3") (pin "4") (pinfunction "4_4") (pintype "passive"))
      (node (ref "Q2") (pin "2") (pinfunction "S_2") (pintype "passive"))
      (node (ref "R28") (pin "1") (pinfunction "1_1") (pintype "passive"))
      (node (ref "R32") (pin "1") (pinfunction "1_1") (pintype "passive"))
      (node (ref "R34") (pin "1") (pinfunction "1_1") (pintype "passive"))
      (node (ref "U10") (pin "2") (pinfunction "GND_2") (pintype "power_in"))
      (node (ref "U3") (pin "5") (pinfunction "GND2_5") (pintype "power_in"))
      (node (ref "U4") (pin "5") (pinfunction "GND2_5") (pintype "power_in"))
      (node (ref "U5") (pin "2") (pinfunction "CONTROL-_2") (pintype "passive"))
      (node (ref "U6") (pin "1") (pinfunction "GND_1") (pintype "power_in"))
    )
    (net (code "5") (name "IP+") (class "Default")
      (node (ref "IP+") (pin "1") (pinfunction "1_1") (pintype "passive"))
      (node (ref "J3") (pin "5") (pinfunction "5_5") (pintype "passive"))
      (node (ref "U4") (pin "7") (pinfunction "OUTP_7") (pintype "output"))
    )
    (net (code "6") (name "IP-") (class "Default")
      (node (ref "IP-") (pin "1") (pinfunction "1_1") (pintype "passive"))
      (node (ref "J3") (pin "6") (pinfunction "6_6") (pintype "passive"))
      (node (ref "U4") (pin "6") (pinfunction "OUTN_6") (pintype "output"))
    )
    (net (code "7") (name "IT+") (class "Default")
      (node (ref "IT+") (pin "1") (pinfunction "1_1") (pintype "passive"))
      (node (ref "J3") (pin "7") (pinfunction "7_7") (pintype "passive"))
      (node (ref "U3") (pin "7") (pinfunction "OUTP_7") (pintype "output"))
    )
    (net (code "8") (name "IT-") (class "Default")
      (node (ref "IT-") (pin "1") (pinfunction "1_1") (pintype "passive"))
      (node (ref "J3") (pin "8") (pinfunction "8_8") (pintype "passive"))
      (node (ref "U3") (pin "6") (pinfunction "OUTN_6") (pintype "output"))
    )
    (net (code "9") (name "LED+") (class "Default")
      (node (ref "J2") (pin "3") (pinfunction "3_3") (pintype "passive"))
      (node (ref "R20") (pin "2") (pinfunction "2_2") (pintype "passive"))
    )
    (net (code "10") (name "Net-(C2-Pad2)") (class "Default")
      (node (ref "C2") (pin "2") (pinfunction "2_2") (pintype "passive"))
      (node (ref "R3") (pin "2") (pinfunction "2_2") (pintype "passive"))
    )
    (net (code "11") (name "Net-(C9-Pad1)") (class "Default")
      (node (ref "C9") (pin "1") (pinfunction "1_1") (pintype "passive"))
      (node (ref "R7") (pin "1") (pinfunction "1_1") (pintype "passive"))
    )
    (net (code "12") (name "Net-(CV1-Pad2)") (class "Default")
      (node (ref "CV1") (pin "2") (pinfunction "2_2") (pintype "passive"))
      (node (ref "R36") (pin "2") (pinfunction "2_2") (pintype "passive"))
    )
    (net (code "13") (name "Net-(D1-A)") (class "Default")
      (node (ref "C2") (pin "1") (pinfunction "1_1") (pintype "passive"))
      (node (ref "D1") (pin "1") (pinfunction "A_1") (pintype "passive"))
      (node (ref "R5") (pin "2") (pinfunction "2_2") (pintype "passive"))
      (node (ref "T1") (pin "5") (pinfunction "5_5") (pintype "bidirectional"))
    )
    (net (code "14") (name "Net-(D1-C)") (class "Default")
      (node (ref "C4") (pin "1") (pinfunction "1_1") (pintype "passive"))
      (node (ref "D1") (pin "2") (pinfunction "C_2") (pintype "passive"))
      (node (ref "U2") (pin "9") (pinfunction "BIAS_9") (pintype "bidirectional"))
    )
    (net (code "15") (name "Net-(D3-A)") (class "Default")
      (node (ref "D3") (pin "2") (pinfunction "A_2") (pintype "passive"))
      (node (ref "R25") (pin "1") (pinfunction "1_1") (pintype "passive"))
    )
    (net (code "16") (name "Net-(D4-A)") (class "Default")
      (node (ref "D4") (pin "2") (pinfunction "A_2") (pintype "passive"))
      (node (ref "R26") (pin "2") (pinfunction "2_2") (pintype "passive"))
    )
    (net (code "17") (name "Net-(D5-A)") (class "Default")
      (node (ref "D5") (pin "2") (pinfunction "A_2") (pintype "passive"))
      (node (ref "R27") (pin "1") (pinfunction "1_1") (pintype "passive"))
    )
    (net (code "18") (name "Net-(D6-A)") (class "Default")
      (node (ref "D6") (pin "2") (pinfunction "A_2") (pintype "passive"))
      (node (ref "R29") (pin "1") (pinfunction "1_1") (pintype "passive"))
    )
    (net (code "19") (name "Net-(D8-A)") (class "Default")
      (node (ref "D8") (pin "2") (pinfunction "A_2") (pintype "passive"))
      (node (ref "R31") (pin "1") (pinfunction "1_1") (pintype "passive"))
    )
    (net (code "20") (name "Net-(D101-A)") (class "Default")
      (node (ref "D101") (pin "1") (pinfunction "A_1") (pintype "passive"))
      (node (ref "R36") (pin "1") (pinfunction "1_1") (pintype "passive"))
      (node (ref "T1") (pin "8") (pinfunction "8,9_8") (pintype "bidirectional"))
      (node (ref "T1") (pin "9") (pinfunction "8,9_9") (pintype "bidirectional"))
    )
    (net (code "21") (name "Net-(D102-C)") (class "Default")
      (node (ref "D102") (pin "2") (pinfunction "C_2") (pintype "passive"))
      (node (ref "D103") (pin "C") (pinfunction "C_C") (pintype "passive"))
    )
    (net (code "22") (name "Net-(D103-PadA)") (class "Default")
      (node (ref "D103") (pin "A") (pinfunction "A_A") (pintype "passive"))
      (node (ref "Q1") (pin "D") (pinfunction "D_D") (pintype "passive"))
      (node (ref "T1") (pin "1") (pinfunction "1_1") (pintype "bidirectional"))
    )
    (net (code "23") (name "Net-(K1-COIL-)") (class "Default")
      (node (ref "D100") (pin "A") (pinfunction "A_A") (pintype "passive"))
      (node (ref "K1") (pin "3") (pinfunction "COIL-_3") (pintype "bidirectional"))
      (node (ref "Q2") (pin "3") (pinfunction "D_3") (pintype "passive"))
    )
    (net (code "24") (name "Net-(K1-CONTACT2)") (class "Default")
      (node (ref "K1") (pin "1") (pinfunction "CONTACT2_1") (pintype "bidirectional"))
      (node (ref "R13") (pin "1") (pinfunction "1_1") (pintype "passive"))
      (node (ref "R23") (pin "1") (pinfunction "1_1") (pintype "passive"))
    )
    (net (code "25") (name "Net-(LED_+12V-A)") (class "Default")
      (node (ref "LED_+12V") (pin "2") (pinfunction "A_2") (pintype "passive"))
      (node (ref "R1") (pin "1") (pinfunction "1_1") (pintype "passive"))
    )
    (net (code "26") (name "Net-(Q1-PadG)") (class "Default")
      (node (ref "Q1") (pin "G") (pinfunction "G_G") (pintype "passive"))
      (node (ref "R4") (pin "2") (pinfunction "2_2") (pintype "passive"))
    )
    (net (code "27") (name "Net-(Q2-G)") (class "Default")
      (node (ref "Q2") (pin "1") (pinfunction "G_1") (pintype "passive"))
      (node (ref "R33") (pin "2") (pinfunction "2_2") (pintype "passive"))
    )
    (net (code "28") (name "Net-(R10-Pad2)") (class "Default")
      (node (ref "R10") (pin "2") (pinfunction "2_2") (pintype "passive"))
      (node (ref "R11") (pin "1") (pinfunction "1_1") (pintype "passive"))
    )
    (net (code "29") (name "Net-(R11-Pad2)") (class "Default")
      (node (ref "R11") (pin "2") (pinfunction "2_2") (pintype "passive"))
      (node (ref "R9") (pin "1") (pinfunction "1_1") (pintype "passive"))
    )
    (net (code "30") (name "Net-(R19-Pad2)") (class "Default")
      (node (ref "R19") (pin "2") (pinfunction "2_2") (pintype "passive"))
      (node (ref "R21") (pin "1") (pinfunction "1_1") (pintype "passive"))
    )
    (net (code "31") (name "Net-(R21-Pad2)") (class "Default")
      (node (ref "R21") (pin "2") (pinfunction "2_2") (pintype "passive"))
      (node (ref "R22") (pin "1") (pinfunction "1_1") (pintype "passive"))
    )
    (net (code "32") (name "Net-(U2-DCM)") (class "Default")
      (node (ref "R3") (pin "1") (pinfunction "1_1") (pintype "passive"))
      (node (ref "U2") (pin "10") (pinfunction "DCM_10") (pintype "bidirectional"))
    )
    (net (code "33") (name "Net-(U2-EN{slash}UVLO)") (class "Default")
      (node (ref "C6") (pin "1") (pinfunction "1_1") (pintype "passive"))
      (node (ref "U2") (pin "17") (pinfunction "EN/UVLO_17") (pintype "bidirectional"))
      (node (ref "U2") (pin "8") (pinfunction "INTVCC_8") (pintype "bidirectional"))
    )
    (net (code "34") (name "Net-(U2-FB)") (class "Default")
      (node (ref "R5") (pin "1") (pinfunction "1_1") (pintype "passive"))
      (node (ref "R6") (pin "2") (pinfunction "2_2") (pintype "passive"))
      (node (ref "U2") (pin "12") (pinfunction "FB_12") (pintype "bidirectional"))
    )
    (net (code "35") (name "Net-(U2-GATE)") (class "Default")
      (node (ref "R4") (pin "1") (pinfunction "1_1") (pintype "passive"))
      (node (ref "U2") (pin "19") (pinfunction "GATE_19") (pintype "bidirectional"))
    )
    (net (code "36") (name "Net-(U2-IREG)") (class "Default")
      (node (ref "R12") (pin "2") (pinfunction "2_2") (pintype "passive"))
      (node (ref "U2") (pin "14") (pinfunction "IREG_14") (pintype "bidirectional"))
    )
    (net (code "37") (name "Net-(U2-SENSE)") (class "Default")
      (node (ref "Q1") (pin "S") (pinfunction "S_S") (pintype "passive"))
      (node (ref "R2") (pin "2") (pinfunction "2_2") (pintype "passive"))
      (node (ref "U2") (pin "18") (pinfunction "SENSE_18") (pintype "bidirectional"))
    )
    (net (code "38") (name "Net-(U2-VC)") (class "Default")
      (node (ref "R7") (pin "2") (pinfunction "2_2") (pintype "passive"))
      (node (ref "U2") (pin "13") (pinfunction "VC_13") (pintype "bidirectional"))
    )
    (net (code "39") (name "Net-(U3-IN)") (class "Default")
      (node (ref "C12") (pin "1") (pinfunction "1_1") (pintype "passive"))
      (node (ref "R15") (pin "2") (pinfunction "2_2") (pintype "passive"))
      (node (ref "U3") (pin "2") (pinfunction "IN_2") (pintype "input"))
    )
    (net (code "40") (name "Net-(U3-VCAP)") (class "Default")
      (node (ref "C16") (pin "1") (pinfunction "1_1") (pintype "passive"))
      (node (ref "U3") (pin "1") (pinfunction "VCAP_1") (pintype "passive"))
    )
    (net (code "41") (name "Net-(U4-IN)") (class "Default")
      (node (ref "C10") (pin "1") (pinfunction "1_1") (pintype "passive"))
      (node (ref "R18") (pin "2") (pinfunction "2_2") (pintype "passive"))
      (node (ref "U4") (pin "2") (pinfunction "IN_2") (pintype "input"))
    )
    (net (code "42") (name "Net-(U4-VCAP)") (class "Default")
      (node (ref "C17") (pin "1") (pinfunction "1_1") (pintype "passive"))
      (node (ref "U4") (pin "1") (pinfunction "VCAP_1") (pintype "passive"))
    )
    (net (code "43") (name "Net-(U5-CONTACT1)") (class "Default")
      (node (ref "R24") (pin "1") (pinfunction "1_1") (pintype "passive"))
      (node (ref "U5") (pin "3") (pinfunction "CONTACT1_3") (pintype "bidirectional"))
    )
    (net (code "44") (name "Net-(U5-CONTROL+)") (class "Default")
      (node (ref "R30") (pin "2") (pinfunction "2_2") (pintype "passive"))
      (node (ref "U5") (pin "1") (pinfunction "CONTROL+_1") (pintype "passive"))
    )
    (net (code "45") (name "Net-(U10-DIV)") (class "Default")
      (node (ref "R34") (pin "2") (pinfunction "2_2") (pintype "passive"))
      (node (ref "R35") (pin "1") (pinfunction "1_1") (pintype "passive"))
      (node (ref "U10") (pin "6") (pinfunction "DIV_6") (pintype "bidirectional"))
    )
    (net (code "46") (name "Net-(U10-SET)") (class "Default")
      (node (ref "R32") (pin "2") (pinfunction "2_2") (pintype "passive"))
      (node (ref "U10") (pin "3") (pinfunction "SET_3") (pintype "bidirectional"))
    )
    (net (code "47") (name "PACK+") (class "Default")
      (node (ref "J1") (pin "5") (pinfunction "5_5") (pintype "passive"))
      (node (ref "K1") (pin "2") (pinfunction "CONTACT1_2") (pintype "bidirectional"))
      (node (ref "PACK+") (pin "1") (pinfunction "1_1") (pintype "passive"))
      (node (ref "U5") (pin "4") (pinfunction "CONTACT2_4") (pintype "bidirectional"))
    )
    (net (code "48") (name "PACK+FUSED") (class "Default")
      (node (ref "PACK+FUSED") (pin "1") (pinfunction "1_1") (pintype "passive"))
      (node (ref "R22") (pin "2") (pinfunction "2_2") (pintype "passive"))
      (node (ref "R24") (pin "2") (pinfunction "2_2") (pintype "passive"))
    )
    (net (code "49") (name "PACK_DIV_OUT") (class "Default")
      (node (ref "PACK_DIV_OUT") (pin "1") (pinfunction "1_1") (pintype "passive"))
      (node (ref "R16") (pin "2") (pinfunction "2_2") (pintype "passive"))
      (node (ref "R17") (pin "2") (pinfunction "2_2") (pintype "passive"))
      (node (ref "R18") (pin "1") (pinfunction "1_1") (pintype "passive"))
      (node (ref "R19") (pin "1") (pinfunction "1_1") (pintype "passive"))
    )
    (net (code "50") (name "PRECHARGE_OK") (class "Default")
      (node (ref "J3") (pin "3") (pinfunction "3_3") (pintype "passive"))
      (node (ref "PRECHARGE_OK") (pin "1") (pinfunction "1_1") (pintype "passive"))
      (node (ref "R29") (pin "2") (pinfunction "2_2") (pintype "passive"))
      (node (ref "U10") (pin "1") (pinfunction "IN_1") (pintype "bidirectional"))
    )
    (net (code "51") (name "SHDN") (class "Default")
      (node (ref "D100") (pin "C") (pinfunction "C_C") (pintype "passive"))
      (node (ref "J3") (pin "2") (pinfunction "2_2") (pintype "passive"))
      (node (ref "K1") (pin "4") (pinfunction "COIL+_4") (pintype "bidirectional"))
      (node (ref "R27") (pin "2") (pinfunction "2_2") (pintype "passive"))
      (node (ref "R30") (pin "1") (pinfunction "1_1") (pintype "passive"))
      (node (ref "SHDN") (pin "1") (pinfunction "1_1") (pintype "passive"))
    )
    (net (code "52") (name "TS+10V") (class "Default")
      (node (ref "C11") (pin "1") (pinfunction "1_1") (pintype "passive"))
      (node (ref "C13") (pin "1") (pinfunction "1_1") (pintype "passive"))
      (node (ref "C15") (pin "1") (pinfunction "1_1") (pintype "passive"))
      (node (ref "C18") (pin "1") (pinfunction "1_1") (pintype "passive"))
      (node (ref "C5") (pin "1") (pinfunction "1_1") (pintype "passive"))
      (node (ref "TS+10V") (pin "1") (pinfunction "1_1") (pintype "passive"))
      (node (ref "U1") (pin "2") (pinfunction "OUT_2") (pintype "power_in"))
      (node (ref "U1") (pin "4") (pinfunction "OUT_4") (pintype "power_in"))
      (node (ref "U3") (pin "3") (pinfunction "VDD1_3") (pintype "power_in"))
      (node (ref "U4") (pin "3") (pinfunction "VDD1_3") (pintype "power_in"))
    )
    (net (code "53") (name "TS+12V") (class "Default")
      (node (ref "C1") (pin "1") (pinfunction "1_1") (pintype "passive"))
      (node (ref "C3") (pin "PLUS") (pinfunction "PLUS_PLUS") (pintype "passive"))
      (node (ref "C7") (pin "1") (pinfunction "1_1") (pintype "passive"))
      (node (ref "C8") (pin "1") (pinfunction "1_1") (pintype "passive"))
      (node (ref "CV1") (pin "1") (pinfunction "1_1") (pintype "passive"))
      (node (ref "D101") (pin "2") (pinfunction "C_2") (pintype "passive"))
      (node (ref "R1") (pin "2") (pinfunction "2_2") (pintype "passive"))
      (node (ref "R20") (pin "1") (pinfunction "1_1") (pintype "passive"))
      (node (ref "TS+12V") (pin "1") (pinfunction "1_1") (pintype "passive"))
      (node (ref "U1") (pin "3") (pinfunction "IN_3") (pintype "power_in"))
    )
    (net (code "54") (name "TS+FUSED") (class "Default")
      (node (ref "C14") (pin "1") (pinfunction "1_1") (pintype "passive"))
      (node (ref "D102") (pin "1") (pinfunction "A_1") (pintype "passive"))
      (node (ref "F1") (pin "3") (pinfunction "2_3") (pintype "passive"))
      (node (ref "F1") (pin "4") (pinfunction "2_4") (pintype "passive"))
      (node (ref "J1") (pin "4") (pinfunction "4_4") (pintype "passive"))
      (node (ref "R9") (pin "2") (pinfunction "2_2") (pintype "passive"))
      (node (ref "T1") (pin "3") (pinfunction "3_3") (pintype "bidirectional"))
      (node (ref "U2") (pin "1") (pinfunction "VIN_1") (pintype "input"))
      (node (ref "U2") (pin "2") (pinfunction "VIN_2") (pintype "input"))
      (node (ref "U2") (pin "3") (pinfunction "VIN_3") (pintype "input"))
    )
    (net (code "55") (name "TS+UNFUSED") (class "Default")
      (node (ref "F1") (pin "1") (pinfunction "1_1") (pintype "passive"))
      (node (ref "F1") (pin "2") (pinfunction "1_2") (pintype "passive"))
      (node (ref "J1") (pin "1") (pinfunction "1_1") (pintype "passive"))
      (node (ref "J1") (pin "2") (pinfunction "2_2") (pintype "passive"))
      (node (ref "R13") (pin "2") (pinfunction "2_2") (pintype "passive"))
      (node (ref "R23") (pin "2") (pinfunction "2_2") (pintype "passive"))
    )
    (net (code "56") (name "TS-FUSED") (class "Default")
      (node (ref "C1") (pin "2") (pinfunction "2_2") (pintype "passive"))
      (node (ref "C10") (pin "2") (pinfunction "2_2") (pintype "passive"))
      (node (ref "C11") (pin "2") (pinfunction "2_2") (pintype "passive"))
      (node (ref "C12") (pin "2") (pinfunction "2_2") (pintype "passive"))
      (node (ref "C13") (pin "2") (pinfunction "2_2") (pintype "passive"))
      (node (ref "C14") (pin "2") (pinfunction "2_2") (pintype "passive"))
      (node (ref "C15") (pin "2") (pinfunction "2_2") (pintype "passive"))
      (node (ref "C16") (pin "2") (pinfunction "2_2") (pintype "passive"))
      (node (ref "C17") (pin "2") (pinfunction "2_2") (pintype "passive"))
      (node (ref "C18") (pin "2") (pinfunction "2_2") (pintype "passive"))
      (node (ref "C3") (pin "MINUS") (pinfunction "MINUS_MINUS") (pintype "passive"))
      (node (ref "C4") (pin "2") (pinfunction "2_2") (pintype "passive"))
      (node (ref "C5") (pin "2") (pinfunction "2_2") (pintype "passive"))
      (node (ref "C6") (pin "2") (pinfunction "2_2") (pintype "passive"))
      (node (ref "C7") (pin "2") (pinfunction "2_2") (pintype "passive"))
      (node (ref "C8") (pin "2") (pinfunction "2_2") (pintype "passive"))
      (node (ref "C9") (pin "2") (pinfunction "2_2") (pintype "passive"))
      (node (ref "F2") (pin "3") (pinfunction "2_3") (pintype "passive"))
      (node (ref "F2") (pin "4") (pinfunction "2_4") (pintype "passive"))
      (node (ref "J2") (pin "1") (pinfunction "1_1") (pintype "passive"))
      (node (ref "J2") (pin "2") (pinfunction "2_2") (pintype "passive"))
      (node (ref "LED_+12V") (pin "1") (pinfunction "C_1") (pintype "passive"))
      (node (ref "R12") (pin "1") (pinfunction "1_1") (pintype "passive"))
      (node (ref "R14") (pin "1") (pinfunction "1_1") (pintype "passive"))
      (node (ref "R16") (pin "1") (pinfunction "1_1") (pintype "passive"))
      (node (ref "R17") (pin "1") (pinfunction "1_1") (pintype "passive"))
      (node (ref "R2") (pin "1") (pinfunction "1_1") (pintype "passive"))
      (node (ref "R6") (pin "1") (pinfunction "1_1") (pintype "passive"))
      (node (ref "R8") (pin "1") (pinfunction "1_1") (pintype "passive"))
      (node (ref "T1") (pin "10") (pinfunction "10,11_10") (pintype "bidirectional"))
      (node (ref "T1") (pin "11") (pinfunction "10,11_11") (pintype "bidirectional"))
      (node (ref "T1") (pin "6") (pinfunction "6_6") (pintype "bidirectional"))
      (node (ref "TS-FUSED") (pin "1") (pinfunction "1_1") (pintype "passive"))
      (node (ref "U1") (pin "1") (pinfunction "GND_1") (pintype "power_in"))
      (node (ref "U2") (pin "15") (pinfunction "GND_15") (pintype "bidirectional"))
      (node (ref "U2") (pin "16") (pinfunction "SMODE_16") (pintype "bidirectional"))
      (node (ref "U2") (pin "20") (pinfunction "GND_20") (pintype "bidirectional"))
      (node (ref "U2") (pin "THERMAL") (pinfunction "P$1_THERMAL") (pintype "output"))
      (node (ref "U3") (pin "4") (pinfunction "GND1_4") (pintype "power_in"))
      (node (ref "U4") (pin "4") (pinfunction "GND1_4") (pintype "power_in"))
    )
    (net (code "57") (name "TS-UNFUSED") (class "Default")
      (node (ref "F2") (pin "1") (pinfunction "1_1") (pintype "passive"))
      (node (ref "F2") (pin "2") (pinfunction "1_2") (pintype "passive"))
      (node (ref "J2") (pin "5") (pinfunction "5_5") (pintype "passive"))
      (node (ref "TS-UNFUSED") (pin "1") (pinfunction "1_1") (pintype "passive"))
    )
    (net (code "58") (name "TS_DIV_OUT") (class "Default")
      (node (ref "R10") (pin "1") (pinfunction "1_1") (pintype "passive"))
      (node (ref "R14") (pin "2") (pinfunction "2_2") (pintype "passive"))
      (node (ref "R15") (pin "1") (pinfunction "1_1") (pintype "passive"))
      (node (ref "R8") (pin "2") (pinfunction "2_2") (pintype "passive"))
      (node (ref "TS_DIV_OUT") (pin "1") (pinfunction "1_1") (pintype "passive"))
    )
    (net (code "59") (name "unconnected-(J1-Pad3)") (class "Default")
      (node (ref "J1") (pin "3") (pinfunction "3_3") (pintype "passive"))
    )
    (net (code "60") (name "unconnected-(J2-Pad4)") (class "Default")
      (node (ref "J2") (pin "4") (pinfunction "4_4") (pintype "passive"))
    )
    (net (code "61") (name "unconnected-(U2-TC-Pad11)") (class "Default")
      (node (ref "U2") (pin "11") (pinfunction "TC_11") (pintype "bidirectional"))
    )
  )
)
